# schematic.net
KiCad netlist of a schematic drawn in EAGLE
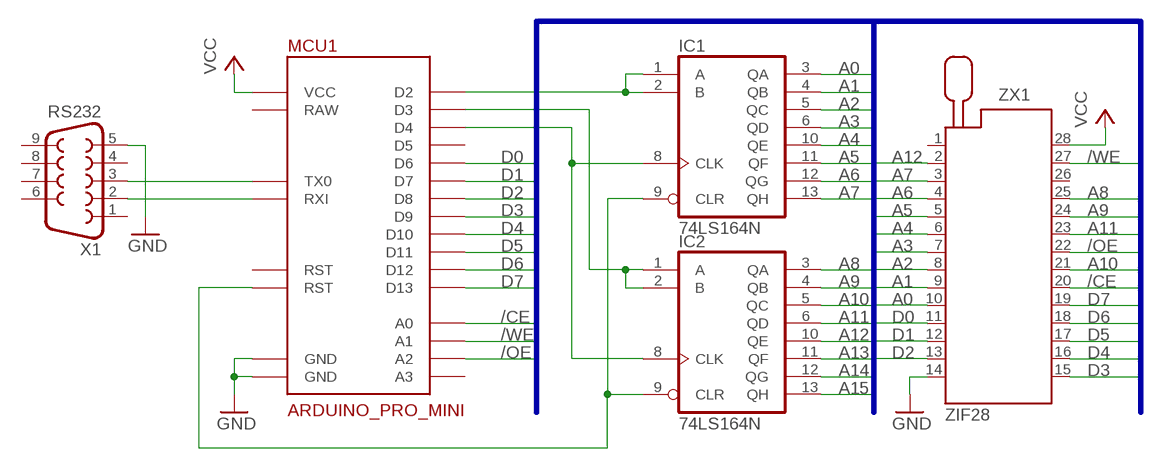
[diagram p0: schematic, sheet 1]

(export (version "E")
  (design (tool "Eeschema 10.0.6"))
  (components
    (comp (ref "IC1")
      (value "74LS164N")
      (footprint "eagle-import:DIL14")
      (libsource (lib "eagle-import") (part "74164NLS"))
    )
    (comp (ref "IC2")
      (value "74LS164N")
      (footprint "eagle-import:DIL14")
      (libsource (lib "eagle-import") (part "74164NLS"))
    )
    (comp (ref "MCU1")
      (value "ARDUINO_PRO_MINI")
      (footprint "eagle-import:PDIP-26")
      (libsource (lib "eagle-import") (part "ARDUINOPROMINI"))
    )
    (comp (ref "X1")
      (value "RS232")
      (footprint "eagle-import:F09H")
      (libsource (lib "eagle-import") (part "F09H"))
    )
    (comp (ref "ZX1")
      (value "ZIF28")
      (footprint "eagle-import:228-1277-00-0602J")
      (fields (field (name "MF") "3M") (field (name "MPN") "228-1277-00-0602J"))
      (libsource (lib "eagle-import") (part "228-?00-0602J1277-"))
    )
  )
  (nets
    (net (code "1") (name "/A0") (class "Default")
      (node (ref "IC1") (pin "3") (pinfunction "QA_3") (pintype "output"))
      (node (ref "ZX1") (pin "10") (pinfunction "10_10") (pintype "passive"))
    )
    (net (code "2") (name "/A1") (class "Default")
      (node (ref "IC1") (pin "4") (pinfunction "QB_4") (pintype "output"))
      (node (ref "ZX1") (pin "9") (pinfunction "9_9") (pintype "passive"))
    )
    (net (code "3") (name "/A2") (class "Default")
      (node (ref "IC1") (pin "5") (pinfunction "QC_5") (pintype "output"))
      (node (ref "ZX1") (pin "8") (pinfunction "8_8") (pintype "passive"))
    )
    (net (code "4") (name "/A3") (class "Default")
      (node (ref "IC1") (pin "6") (pinfunction "QD_6") (pintype "output"))
      (node (ref "ZX1") (pin "7") (pinfunction "7_7") (pintype "passive"))
    )
    (net (code "5") (name "/A4") (class "Default")
      (node (ref "IC1") (pin "10") (pinfunction "QE_10") (pintype "output"))
      (node (ref "ZX1") (pin "6") (pinfunction "6_6") (pintype "passive"))
    )
    (net (code "6") (name "/A5") (class "Default")
      (node (ref "IC1") (pin "11") (pinfunction "QF_11") (pintype "output"))
      (node (ref "ZX1") (pin "5") (pinfunction "5_5") (pintype "passive"))
    )
    (net (code "7") (name "/A6") (class "Default")
      (node (ref "IC1") (pin "12") (pinfunction "QG_12") (pintype "output"))
      (node (ref "ZX1") (pin "4") (pinfunction "4_4") (pintype "passive"))
    )
    (net (code "8") (name "/A7") (class "Default")
      (node (ref "IC1") (pin "13") (pinfunction "QH_13") (pintype "output"))
      (node (ref "ZX1") (pin "3") (pinfunction "3_3") (pintype "passive"))
    )
    (net (code "9") (name "/A8") (class "Default")
      (node (ref "IC2") (pin "3") (pinfunction "QA_3") (pintype "output"))
      (node (ref "ZX1") (pin "25") (pinfunction "25_25") (pintype "passive"))
    )
    (net (code "10") (name "/A9") (class "Default")
      (node (ref "IC2") (pin "4") (pinfunction "QB_4") (pintype "output"))
      (node (ref "ZX1") (pin "24") (pinfunction "24_24") (pintype "passive"))
    )
    (net (code "11") (name "/A10") (class "Default")
      (node (ref "IC2") (pin "5") (pinfunction "QC_5") (pintype "output"))
      (node (ref "ZX1") (pin "21") (pinfunction "21_21") (pintype "passive"))
    )
    (net (code "12") (name "/A11") (class "Default")
      (node (ref "IC2") (pin "6") (pinfunction "QD_6") (pintype "output"))
      (node (ref "ZX1") (pin "23") (pinfunction "23_23") (pintype "passive"))
    )
    (net (code "13") (name "/A12") (class "Default")
      (node (ref "IC2") (pin "10") (pinfunction "QE_10") (pintype "output"))
      (node (ref "ZX1") (pin "2") (pinfunction "2_2") (pintype "passive"))
    )
    (net (code "14") (name "/A13") (class "Default")
      (node (ref "IC2") (pin "11") (pinfunction "QF_11") (pintype "output"))
    )
    (net (code "15") (name "/A14") (class "Default")
      (node (ref "IC2") (pin "12") (pinfunction "QG_12") (pintype "output"))
    )
    (net (code "16") (name "/A15") (class "Default")
      (node (ref "IC2") (pin "13") (pinfunction "QH_13") (pintype "output"))
    )
    (net (code "17") (name "/D0") (class "Default")
      (node (ref "MCU1") (pin "D6") (pinfunction "D6_D6") (pintype "bidirectional"))
      (node (ref "ZX1") (pin "11") (pinfunction "11_11") (pintype "passive"))
    )
    (net (code "18") (name "/D1") (class "Default")
      (node (ref "MCU1") (pin "D7") (pinfunction "D7_D7") (pintype "bidirectional"))
      (node (ref "ZX1") (pin "12") (pinfunction "12_12") (pintype "passive"))
    )
    (net (code "19") (name "/D2") (class "Default")
      (node (ref "MCU1") (pin "D8") (pinfunction "D8_D8") (pintype "bidirectional"))
      (node (ref "ZX1") (pin "13") (pinfunction "13_13") (pintype "passive"))
    )
    (net (code "20") (name "/D3") (class "Default")
      (node (ref "MCU1") (pin "D9") (pinfunction "D9_D9") (pintype "bidirectional"))
      (node (ref "ZX1") (pin "15") (pinfunction "15_15") (pintype "passive"))
    )
    (net (code "21") (name "/D4") (class "Default")
      (node (ref "MCU1") (pin "D10") (pinfunction "D10_D10") (pintype "bidirectional"))
      (node (ref "ZX1") (pin "16") (pinfunction "16_16") (pintype "passive"))
    )
    (net (code "22") (name "/D5") (class "Default")
      (node (ref "MCU1") (pin "D11") (pinfunction "D11_D11") (pintype "bidirectional"))
      (node (ref "ZX1") (pin "17") (pinfunction "17_17") (pintype "passive"))
    )
    (net (code "23") (name "/D6") (class "Default")
      (node (ref "MCU1") (pin "D12") (pinfunction "D12_D12") (pintype "bidirectional"))
      (node (ref "ZX1") (pin "18") (pinfunction "18_18") (pintype "passive"))
    )
    (net (code "24") (name "/D7") (class "Default")
      (node (ref "MCU1") (pin "D13") (pinfunction "D13_D13") (pintype "bidirectional"))
      (node (ref "ZX1") (pin "19") (pinfunction "19_19") (pintype "passive"))
    )
    (net (code "25") (name "/RAW") (class "Default")
      (node (ref "MCU1") (pin "RAW") (pinfunction "RAW_RAW") (pintype "power_in"))
    )
    (net (code "26") (name "/{slash}CE") (class "Default")
      (node (ref "MCU1") (pin "A0") (pinfunction "A0_A0") (pintype "bidirectional"))
      (node (ref "ZX1") (pin "20") (pinfunction "20_20") (pintype "passive"))
    )
    (net (code "27") (name "/{slash}OE") (class "Default")
      (node (ref "MCU1") (pin "A2") (pinfunction "A2_A2") (pintype "bidirectional"))
      (node (ref "ZX1") (pin "22") (pinfunction "22_22") (pintype "passive"))
    )
    (net (code "28") (name "/{slash}WE") (class "Default")
      (node (ref "MCU1") (pin "A1") (pinfunction "A1_A1") (pintype "bidirectional"))
      (node (ref "ZX1") (pin "27") (pinfunction "27_27") (pintype "passive"))
    )
    (net (code "29") (name "GND") (class "Default")
      (node (ref "MCU1") (pin "GND") (pinfunction "GND_GND") (pintype "power_in"))
      (node (ref "MCU1") (pin "GND0") (pinfunction "GND_GND0") (pintype "power_in"))
      (node (ref "X1") (pin "5") (pinfunction "5_5") (pintype "passive"))
      (node (ref "ZX1") (pin "14") (pinfunction "14_14") (pintype "passive"))
    )
    (net (code "30") (name "Net-(IC1A-A)") (class "Default")
      (node (ref "IC1") (pin "1") (pinfunction "A_1") (pintype "input"))
      (node (ref "IC1") (pin "2") (pinfunction "B_2") (pintype "input"))
      (node (ref "MCU1") (pin "D2") (pinfunction "D2_D2") (pintype "bidirectional"))
    )
    (net (code "31") (name "Net-(IC1A-CLK)") (class "Default")
      (node (ref "IC1") (pin "8") (pinfunction "CLK_8") (pintype "input"))
      (node (ref "IC2") (pin "8") (pinfunction "CLK_8") (pintype "input"))
      (node (ref "MCU1") (pin "D4") (pinfunction "D4_D4") (pintype "bidirectional"))
    )
    (net (code "32") (name "Net-(IC1A-CLR)") (class "Default")
      (node (ref "IC1") (pin "9") (pinfunction "CLR_9") (pintype "input"))
      (node (ref "IC2") (pin "9") (pinfunction "CLR_9") (pintype "input"))
      (node (ref "MCU1") (pin "RST") (pinfunction "RST_RST") (pintype "bidirectional"))
    )
    (net (code "33") (name "Net-(IC2A-A)") (class "Default")
      (node (ref "IC2") (pin "1") (pinfunction "A_1") (pintype "input"))
      (node (ref "IC2") (pin "2") (pinfunction "B_2") (pintype "input"))
      (node (ref "MCU1") (pin "D3") (pinfunction "D3_D3") (pintype "bidirectional"))
    )
    (net (code "34") (name "Net-(MCU1-PadRXI)") (class "Default")
      (node (ref "MCU1") (pin "RXI") (pinfunction "RXI_RXI") (pintype "input"))
      (node (ref "X1") (pin "2") (pinfunction "2_2") (pintype "passive"))
    )
    (net (code "35") (name "Net-(MCU1-TX0)") (class "Default")
      (node (ref "MCU1") (pin "TXO") (pinfunction "TX0_TXO") (pintype "output"))
      (node (ref "X1") (pin "3") (pinfunction "3_3") (pintype "passive"))
    )
    (net (code "36") (name "VCC") (class "Default")
      (node (ref "MCU1") (pin "VCC") (pinfunction "VCC_VCC") (pintype "power_in"))
      (node (ref "ZX1") (pin "28") (pinfunction "28_28") (pintype "passive"))
    )
    (net (code "37") (name "unconnected-(MCU1-PadA3)") (class "Default")
      (node (ref "MCU1") (pin "A3") (pinfunction "A3_A3") (pintype "bidirectional"))
    )
    (net (code "38") (name "unconnected-(MCU1-PadD5)") (class "Default")
      (node (ref "MCU1") (pin "D5") (pinfunction "D5_D5") (pintype "bidirectional"))
    )
    (net (code "39") (name "unconnected-(MCU1-RST-PadRST0)") (class "Default")
      (node (ref "MCU1") (pin "RST0") (pinfunction "RST_RST0") (pintype "bidirectional"))
    )
    (net (code "40") (name "unconnected-(X1-Pad1)") (class "Default")
      (node (ref "X1") (pin "1") (pinfunction "1_1") (pintype "passive"))
    )
    (net (code "41") (name "unconnected-(X1-Pad4)") (class "Default")
      (node (ref "X1") (pin "4") (pinfunction "4_4") (pintype "passive"))
    )
    (net (code "42") (name "unconnected-(X1-Pad6)") (class "Default")
      (node (ref "X1") (pin "6") (pinfunction "6_6") (pintype "passive"))
    )
    (net (code "43") (name "unconnected-(X1-Pad7)") (class "Default")
      (node (ref "X1") (pin "7") (pinfunction "7_7") (pintype "passive"))
    )
    (net (code "44") (name "unconnected-(X1-Pad8)") (class "Default")
      (node (ref "X1") (pin "8") (pinfunction "8_8") (pintype "passive"))
    )
    (net (code "45") (name "unconnected-(X1-Pad9)") (class "Default")
      (node (ref "X1") (pin "9") (pinfunction "9_9") (pintype "passive"))
    )
    (net (code "46") (name "unconnected-(ZX1-Pad1)") (class "Default")
      (node (ref "ZX1") (pin "1") (pinfunction "1_1") (pintype "passive"))
    )
    (net (code "47") (name "unconnected-(ZX1-Pad26)") (class "Default")
      (node (ref "ZX1") (pin "26") (pinfunction "26_26") (pintype "passive"))
    )
  )
)
